# CW-LINK.net
KiCad netlist of a schematic drawn in EasyEDA Pro
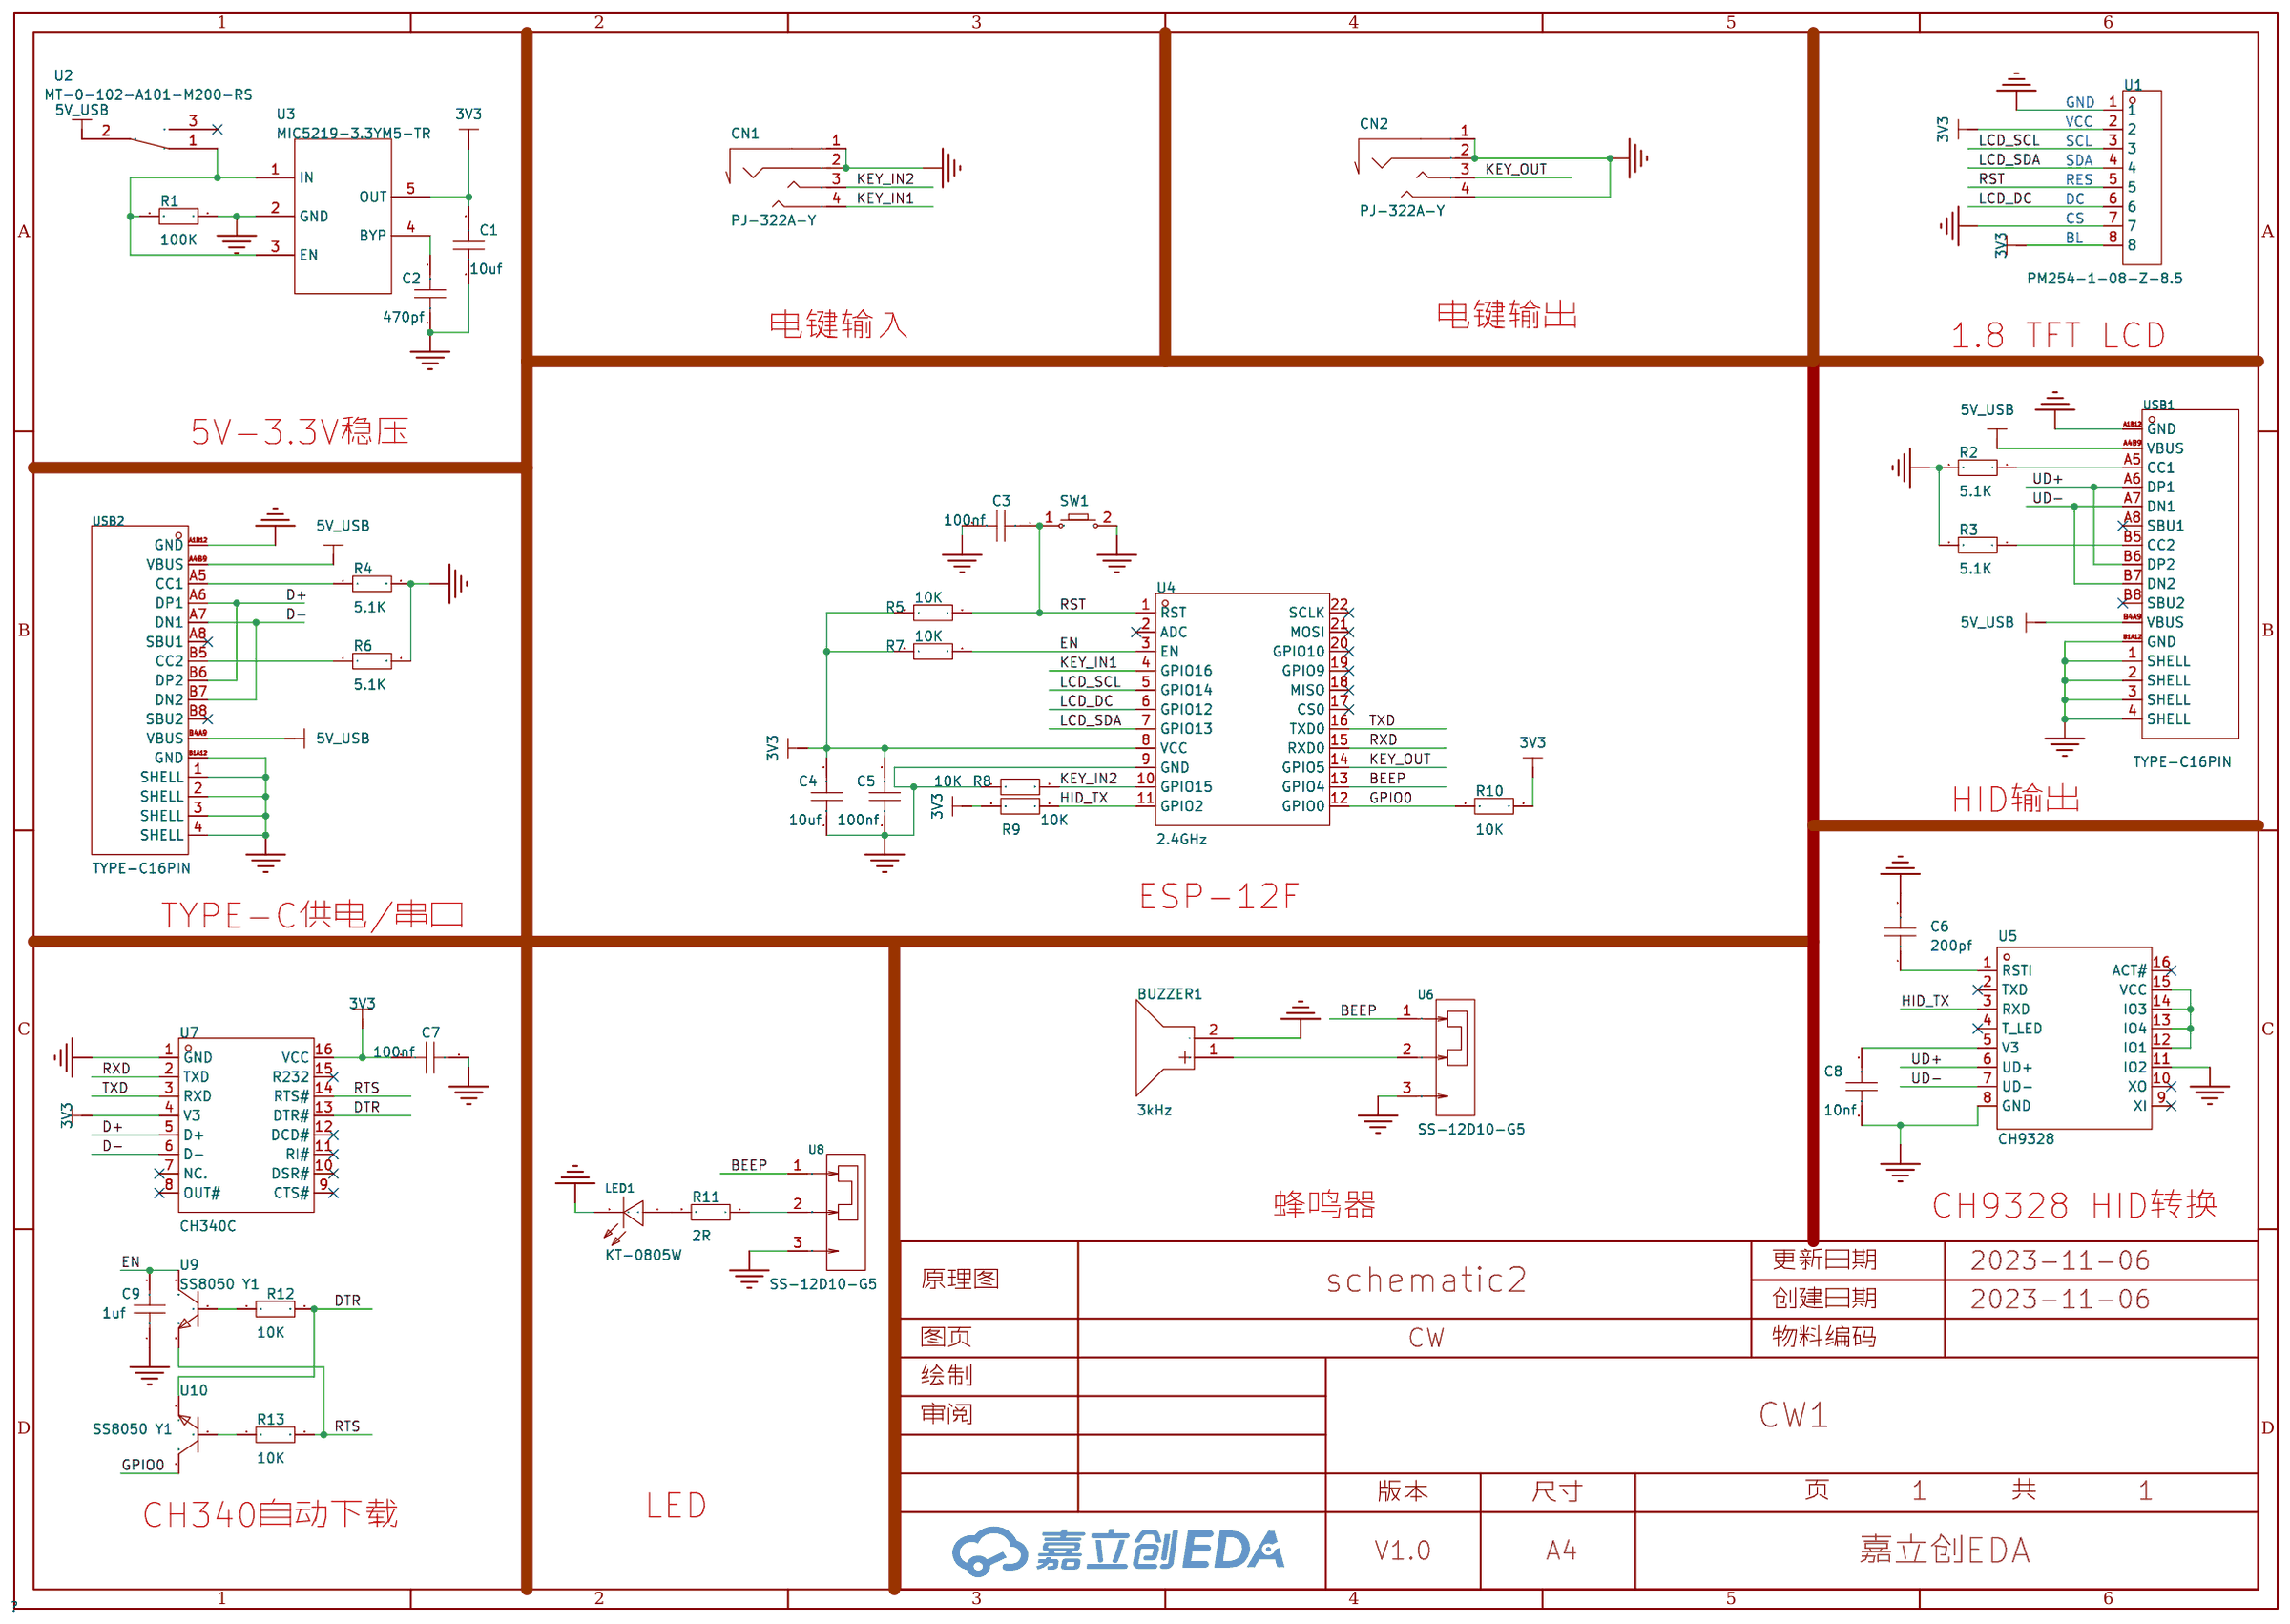
[diagram p0: schematic sheet]

(export (version "E")
  (design (tool "Eeschema 10.0.6"))
  (components
    (comp (ref "BUZZER1")
      (value "3kHz")
      (footprint "easyedapro:BUZ-TH_BD9.0-P5.00-D0.6-FD")
      (fields (field (name "Manufacturer Part") "HNB09A03") (field (name "Manufacturer") "华能"))
      (libsource (lib "easyedapro") (part "HNB09A03"))
    )
    (comp (ref "C1")
      (value "10uf")
      (footprint "easyedapro:C0603")
      (libsource (lib "easyedapro") (part "CapAcitance"))
    )
    (comp (ref "C2")
      (value "470pf")
      (footprint "easyedapro:C0603")
      (libsource (lib "easyedapro") (part "CapAcitance"))
    )
    (comp (ref "C3")
      (value "100nf")
      (footprint "easyedapro:C0603")
      (libsource (lib "easyedapro") (part "CapAcitance"))
    )
    (comp (ref "C4")
      (value "10uf")
      (footprint "easyedapro:C0603")
      (libsource (lib "easyedapro") (part "CapAcitance"))
    )
    (comp (ref "C5")
      (value "100nf")
      (footprint "easyedapro:C0603")
      (libsource (lib "easyedapro") (part "CapAcitance"))
    )
    (comp (ref "C6")
      (value "200pf")
      (footprint "easyedapro:C0603")
      (libsource (lib "easyedapro") (part "CapAcitance"))
    )
    (comp (ref "C7")
      (value "100nf")
      (footprint "easyedapro:C0603")
      (libsource (lib "easyedapro") (part "CapAcitance"))
    )
    (comp (ref "C8")
      (value "10nf")
      (footprint "easyedapro:C0603")
      (libsource (lib "easyedapro") (part "CapAcitance"))
    )
    (comp (ref "C9")
      (value "1uf")
      (footprint "easyedapro:C0603")
      (libsource (lib "easyedapro") (part "CapAcitance"))
    )
    (comp (ref "CN1")
      (value "PJ-322A-Y")
      (footprint "easyedapro:AUDIO-TH_PJ-322A-Y")
      (description "连接器类型:3.5mm耳机座;额定电流:500mA;额定电压:30V;工作温度范围:-20°C~+70°C;焊接温度(最大值):235°C;")
      (fields (field (name "Manufacturer") "XKB Connectivity(中国星坤)"))
      (libsource (lib "easyedapro") (part "PJ-322A-Y"))
    )
    (comp (ref "CN2")
      (value "PJ-322A-Y")
      (footprint "easyedapro:AUDIO-TH_PJ-322A-Y")
      (description "连接器类型:3.5mm耳机座;额定电流:500mA;额定电压:30V;工作温度范围:-20°C~+70°C;焊接温度(最大值):235°C;")
      (fields (field (name "Manufacturer") "XKB Connectivity(中国星坤)"))
      (libsource (lib "easyedapro") (part "PJ-322A-Y"))
    )
    (comp (ref "LED1")
      (value "KT-0805W")
      (footprint "easyedapro:LED0805-R-RD")
      (description "色温6000K左右")
      (fields (field (name "Manufacturer") "KENTO"))
      (libsource (lib "easyedapro") (part "whiteLEDSMD"))
    )
    (comp (ref "R1") (value "100K") (footprint "easyedapro:R0603") (libsource (lib "easyedapro") (part "电阻")))
    (comp (ref "R2") (value "5.1K") (footprint "easyedapro:R0603") (libsource (lib "easyedapro") (part "电阻")))
    (comp (ref "R3") (value "5.1K") (footprint "easyedapro:R0603") (libsource (lib "easyedapro") (part "电阻")))
    (comp (ref "R4") (value "5.1K") (footprint "easyedapro:R0603") (libsource (lib "easyedapro") (part "电阻")))
    (comp (ref "R5") (value "10K") (footprint "easyedapro:R0603") (libsource (lib "easyedapro") (part "电阻")))
    (comp (ref "R6") (value "5.1K") (footprint "easyedapro:R0603") (libsource (lib "easyedapro") (part "电阻")))
    (comp (ref "R7") (value "10K") (footprint "easyedapro:R0603") (libsource (lib "easyedapro") (part "电阻")))
    (comp (ref "R8") (value "10K") (footprint "easyedapro:R0603") (libsource (lib "easyedapro") (part "电阻")))
    (comp (ref "R9") (value "10K") (footprint "easyedapro:R0603") (libsource (lib "easyedapro") (part "电阻")))
    (comp (ref "R10") (value "10K") (footprint "easyedapro:R0603") (libsource (lib "easyedapro") (part "电阻")))
    (comp (ref "R11") (value "2R") (footprint "easyedapro:R0603") (libsource (lib "easyedapro") (part "电阻")))
    (comp (ref "R12") (value "10K") (footprint "easyedapro:R0603") (libsource (lib "easyedapro") (part "电阻")))
    (comp (ref "R13") (value "10K") (footprint "easyedapro:R0603") (libsource (lib "easyedapro") (part "电阻")))
    (comp (ref "SW1")
      (value "~")
      (footprint "easyedapro:Key_SMD_3x4x2")
      (libsource (lib "easyedapro") (part "轻触按键x2"))
    )
    (comp (ref "U1")
      (value "PM254-1-08-Z-8.5")
      (footprint "easyedapro:HDR-TH_8P-P2.54-V-F")
      (fields (field (name "Manufacturer") "HCTL(华灿天禄)"))
      (libsource (lib "easyedapro") (part "PM254-1-08-Z-8.5"))
    )
    (comp (ref "U2")
      (value "MT-0-102-A101-M200-RS")
      (footprint "easyedapro:SW-TH_MT-0-103-A101-M200-RS")
      (description "额定电流:5A;额定电压(AC):125V;电路结构:单刀双掷;机械寿命:-;安装方式:直插;")
      (fields (field (name "Manufacturer") "YUEN FUNG(源丰)"))
      (libsource (lib "easyedapro") (part "MT-0-102-A101-M200-RS+PJ"))
    )
    (comp (ref "U3")
      (value "MIC5219-3.3YM5-TR")
      (footprint "easyedapro:SOT-23-5_L3.0-W1.7-P0.95-LS2.8-TL")
      (description "输出类型:-;")
      (fields (field (name "Manufacturer") "MICROCHIP(美国微芯)"))
      (libsource (lib "easyedapro") (part "MIC5219-3.3YM5"))
    )
    (comp (ref "U4")
      (value "2.4GHz")
      (footprint "easyedapro:WIFIM-SMD_ESP-12F-ESP8266MOD")
      (description "频率:2.4GHz;发射功率:16dBm;核心处理器:ESP8266;天线形式:PCB 板载天线;接收灵敏度:-90dBm;")
      (fields
        (field (name "Manufacturer Part") "ESP-12F(ESP8266MOD)")
        (field (name "Manufacturer") "Ai-Thinker(安信可)")
      )
      (libsource (lib "easyedapro") (part "ESP-12F(ESP8266MOD)"))
    )
    (comp (ref "U5")
      (value "CH9328")
      (footprint "easyedapro:SOP-16_L10.0-W3.9-P1.27-LS6.0-BL")
      (description "应用功能:收发器;接口协议:USB 2.0;数据速率:12Mbps;")
      (fields (field (name "Manufacturer") "WCH(南京沁恒)"))
      (libsource (lib "easyedapro") (part "CH9328"))
    )
    (comp (ref "U6")
      (value "SS-12D10-G5")
      (footprint "easyedapro:SW-TH_SS-12D10-G050")
      (description "电路结构:单刀双掷;安装方式:直插;机械寿命:-;开关颜色:黑色;")
      (fields (field (name "Manufacturer") "DEALON(德艺隆)"))
      (libsource (lib "easyedapro") (part "SS-12D10-G5"))
    )
    (comp (ref "U7")
      (value "CH340C")
      (footprint "easyedapro:SOP-16_L10.0-W3.9-P1.27-LS6.0-BL")
      (description "应用功能:收发器;接口协议:USB 2.0;数据速率:2Mbps;")
      (fields (field (name "Manufacturer") "WCH(南京沁恒)"))
      (libsource (lib "easyedapro") (part "CH340C"))
    )
    (comp (ref "U8")
      (value "SS-12D10-G5")
      (footprint "easyedapro:SW-TH_SS-12D10-G050")
      (description "电路结构:单刀双掷;安装方式:直插;机械寿命:-;开关颜色:黑色;")
      (fields (field (name "Manufacturer") "DEALON(德艺隆)"))
      (libsource (lib "easyedapro") (part "SS-12D10-G5"))
    )
    (comp (ref "U9")
      (value "SS8050 Y1")
      (footprint "easyedapro:SOT-23-3_L2.9-W1.3-P1.90-LS2.4-BR")
      (description "晶体管类型:NPN;集射极击穿电压(Vceo):25V;集电极电流(Ic):1.5A;功率(Pd):300mW;直流电流增益(hFE@Ic,Vce):120@100mA,1V;")
      (fields (field (name "Manufacturer") "JUXING(钜兴)"))
      (libsource (lib "easyedapro") (part "SS8050 Y1"))
    )
    (comp (ref "U10")
      (value "SS8050 Y1")
      (footprint "easyedapro:SOT-23-3_L2.9-W1.3-P1.90-LS2.4-BR")
      (description "晶体管类型:NPN;集射极击穿电压(Vceo):25V;集电极电流(Ic):1.5A;功率(Pd):300mW;直流电流增益(hFE@Ic,Vce):120@100mA,1V;")
      (fields (field (name "Manufacturer") "JUXING(钜兴)"))
      (libsource (lib "easyedapro") (part "SS8050 Y1"))
    )
    (comp (ref "USB1")
      (value "TYPE-C16PIN")
      (footprint "easyedapro:USB-C-SMD_TYPE-C16PIN")
      (description "连接器类型:Type-C;标准:-;公母:母座;触点数量:16P;端口数量:1;安装方式:卧贴;额定电流 - 电源:3A;工作温度范围:-40°C~+85°C;")
      (fields (field (name "Manufacturer") "SHOU HAN(首韩)"))
      (libsource (lib "easyedapro") (part "TYPE-C16PIN"))
    )
    (comp (ref "USB2")
      (value "TYPE-C16PIN")
      (footprint "easyedapro:USB-C-SMD_TYPE-C16PIN")
      (description "连接器类型:Type-C;标准:-;公母:母座;触点数量:16P;端口数量:1;安装方式:卧贴;额定电流 - 电源:3A;工作温度范围:-40°C~+85°C;")
      (fields (field (name "Manufacturer") "SHOU HAN(首韩)"))
      (libsource (lib "easyedapro") (part "TYPE-C16PIN"))
    )
  )
  (nets
    (net (code "1") (name "/BEEP") (class "Default")
      (node (ref "U4") (pin "13") (pinfunction "GPIO4_13") (pintype "input"))
      (node (ref "U6") (pin "1") (pinfunction "1_1") (pintype "input"))
      (node (ref "U8") (pin "1") (pinfunction "1_1") (pintype "input"))
    )
    (net (code "2") (name "/D+") (class "Default")
      (node (ref "U7") (pin "5") (pinfunction "D+_5") (pintype "unspecified"))
      (node (ref "USB2") (pin "A6") (pinfunction "DP1_A6") (pintype "input"))
      (node (ref "USB2") (pin "B6") (pinfunction "DP2_B6") (pintype "input"))
    )
    (net (code "3") (name "/D-") (class "Default")
      (node (ref "U7") (pin "6") (pinfunction "D-_6") (pintype "unspecified"))
      (node (ref "USB2") (pin "A7") (pinfunction "DN1_A7") (pintype "input"))
      (node (ref "USB2") (pin "B7") (pinfunction "DN2_B7") (pintype "input"))
    )
    (net (code "4") (name "/DTR") (class "Default")
      (node (ref "R12") (pin "2") (pinfunction "2_2") (pintype "input"))
      (node (ref "U10") (pin "2") (pinfunction "E_2") (pintype "input"))
      (node (ref "U7") (pin "13") (pinfunction "DTR#_13") (pintype "unspecified"))
    )
    (net (code "5") (name "/EN") (class "Default")
      (node (ref "C9") (pin "2") (pinfunction "2_2") (pintype "input"))
      (node (ref "R7") (pin "2") (pinfunction "2_2") (pintype "input"))
      (node (ref "U4") (pin "3") (pinfunction "EN_3") (pintype "input"))
      (node (ref "U9") (pin "3") (pinfunction "C_3") (pintype "input"))
    )
    (net (code "6") (name "/GPIO0") (class "Default")
      (node (ref "R10") (pin "1") (pinfunction "1_1") (pintype "input"))
      (node (ref "U10") (pin "3") (pinfunction "C_3") (pintype "input"))
      (node (ref "U4") (pin "12") (pinfunction "GPIO0_12") (pintype "input"))
    )
    (net (code "7") (name "/HID_TX") (class "Default")
      (node (ref "R9") (pin "1") (pinfunction "1_1") (pintype "input"))
      (node (ref "U4") (pin "11") (pinfunction "GPIO2_11") (pintype "input"))
      (node (ref "U5") (pin "3") (pinfunction "RXD_3") (pintype "unspecified"))
    )
    (net (code "8") (name "/KEY_IN1") (class "Default")
      (node (ref "CN1") (pin "4") (pinfunction "4_4") (pintype "input"))
      (node (ref "U4") (pin "4") (pinfunction "GPIO16_4") (pintype "input"))
    )
    (net (code "9") (name "/KEY_IN2") (class "Default")
      (node (ref "CN1") (pin "3") (pinfunction "3_3") (pintype "input"))
      (node (ref "R8") (pin "2") (pinfunction "2_2") (pintype "input"))
      (node (ref "U4") (pin "10") (pinfunction "GPIO15_10") (pintype "input"))
    )
    (net (code "10") (name "/KEY_OUT") (class "Default")
      (node (ref "CN2") (pin "3") (pinfunction "3_3") (pintype "input"))
      (node (ref "U4") (pin "14") (pinfunction "GPIO5_14") (pintype "input"))
    )
    (net (code "11") (name "/LCD_DC") (class "Default")
      (node (ref "U1") (pin "6") (pinfunction "6_6") (pintype "unspecified"))
      (node (ref "U4") (pin "6") (pinfunction "GPIO12_6") (pintype "input"))
    )
    (net (code "12") (name "/LCD_SCL") (class "Default")
      (node (ref "U1") (pin "3") (pinfunction "3_3") (pintype "unspecified"))
      (node (ref "U4") (pin "5") (pinfunction "GPIO14_5") (pintype "input"))
    )
    (net (code "13") (name "/LCD_SDA") (class "Default")
      (node (ref "U1") (pin "4") (pinfunction "4_4") (pintype "unspecified"))
      (node (ref "U4") (pin "7") (pinfunction "GPIO13_7") (pintype "input"))
    )
    (net (code "14") (name "/RST") (class "Default")
      (node (ref "C3") (pin "1") (pinfunction "1_1") (pintype "input"))
      (node (ref "R5") (pin "2") (pinfunction "2_2") (pintype "input"))
      (node (ref "SW1") (pin "1") (pinfunction "1_1") (pintype "input"))
      (node (ref "U1") (pin "5") (pinfunction "5_5") (pintype "unspecified"))
      (node (ref "U4") (pin "1") (pinfunction "RST_1") (pintype "input"))
    )
    (net (code "15") (name "/RTS") (class "Default")
      (node (ref "R13") (pin "2") (pinfunction "2_2") (pintype "input"))
      (node (ref "U7") (pin "14") (pinfunction "RTS#_14") (pintype "unspecified"))
      (node (ref "U9") (pin "2") (pinfunction "E_2") (pintype "input"))
    )
    (net (code "16") (name "/RXD") (class "Default")
      (node (ref "U4") (pin "15") (pinfunction "RXD0_15") (pintype "input"))
      (node (ref "U7") (pin "2") (pinfunction "TXD_2") (pintype "unspecified"))
    )
    (net (code "17") (name "/TXD") (class "Default")
      (node (ref "U4") (pin "16") (pinfunction "TXD0_16") (pintype "input"))
      (node (ref "U7") (pin "3") (pinfunction "RXD_3") (pintype "unspecified"))
    )
    (net (code "18") (name "/UD+") (class "Default")
      (node (ref "U5") (pin "6") (pinfunction "UD+_6") (pintype "unspecified"))
      (node (ref "USB1") (pin "A6") (pinfunction "DP1_A6") (pintype "input"))
      (node (ref "USB1") (pin "B6") (pinfunction "DP2_B6") (pintype "input"))
    )
    (net (code "19") (name "/UD-") (class "Default")
      (node (ref "U5") (pin "7") (pinfunction "UD-_7") (pintype "unspecified"))
      (node (ref "USB1") (pin "A7") (pinfunction "DN1_A7") (pintype "input"))
      (node (ref "USB1") (pin "B7") (pinfunction "DN2_B7") (pintype "input"))
    )
    (net (code "20") (name "3V3") (class "Default")
      (node (ref "C1") (pin "2") (pinfunction "2_2") (pintype "input"))
      (node (ref "C4") (pin "2") (pinfunction "2_2") (pintype "input"))
      (node (ref "C5") (pin "2") (pinfunction "2_2") (pintype "input"))
      (node (ref "C7") (pin "1") (pinfunction "1_1") (pintype "input"))
      (node (ref "R10") (pin "2") (pinfunction "2_2") (pintype "input"))
      (node (ref "R5") (pin "1") (pinfunction "1_1") (pintype "input"))
      (node (ref "R7") (pin "1") (pinfunction "1_1") (pintype "input"))
      (node (ref "R9") (pin "2") (pinfunction "2_2") (pintype "input"))
      (node (ref "U1") (pin "2") (pinfunction "2_2") (pintype "unspecified"))
      (node (ref "U1") (pin "8") (pinfunction "8_8") (pintype "unspecified"))
      (node (ref "U3") (pin "5") (pinfunction "OUT_5") (pintype "input"))
      (node (ref "U4") (pin "8") (pinfunction "VCC_8") (pintype "input"))
      (node (ref "U7") (pin "16") (pinfunction "VCC_16") (pintype "unspecified"))
      (node (ref "U7") (pin "4") (pinfunction "V3_4") (pintype "unspecified"))
    )
    (net (code "21") (name "5V_USB") (class "Default")
      (node (ref "U2") (pin "2") (pinfunction "2_2") (pintype "unspecified"))
      (node (ref "USB1") (pin "A4B9") (pinfunction "VBUS_A4B9") (pintype "input"))
      (node (ref "USB1") (pin "B4A9") (pinfunction "VBUS_B4A9") (pintype "input"))
      (node (ref "USB2") (pin "A4B9") (pinfunction "VBUS_A4B9") (pintype "input"))
      (node (ref "USB2") (pin "B4A9") (pinfunction "VBUS_B4A9") (pintype "input"))
    )
    (net (code "22") (name "GND") (class "Default")
      (node (ref "BUZZER1") (pin "2") (pinfunction "-_2") (pintype "input"))
      (node (ref "C1") (pin "1") (pinfunction "1_1") (pintype "input"))
      (node (ref "C2") (pin "1") (pinfunction "1_1") (pintype "input"))
      (node (ref "C3") (pin "2") (pinfunction "2_2") (pintype "input"))
      (node (ref "C4") (pin "1") (pinfunction "1_1") (pintype "input"))
      (node (ref "C5") (pin "1") (pinfunction "1_1") (pintype "input"))
      (node (ref "C6") (pin "2") (pinfunction "2_2") (pintype "input"))
      (node (ref "C7") (pin "2") (pinfunction "2_2") (pintype "input"))
      (node (ref "C8") (pin "1") (pinfunction "1_1") (pintype "input"))
      (node (ref "C9") (pin "1") (pinfunction "1_1") (pintype "input"))
      (node (ref "CN1") (pin "1") (pinfunction "1_1") (pintype "input"))
      (node (ref "CN1") (pin "2") (pinfunction "2_2") (pintype "input"))
      (node (ref "CN2") (pin "1") (pinfunction "1_1") (pintype "input"))
      (node (ref "CN2") (pin "2") (pinfunction "2_2") (pintype "input"))
      (node (ref "CN2") (pin "4") (pinfunction "4_4") (pintype "input"))
      (node (ref "LED1") (pin "2") (pinfunction "K_2") (pintype "input"))
      (node (ref "R1") (pin "1") (pinfunction "1_1") (pintype "input"))
      (node (ref "R2") (pin "2") (pinfunction "2_2") (pintype "input"))
      (node (ref "R3") (pin "2") (pinfunction "2_2") (pintype "input"))
      (node (ref "R4") (pin "2") (pinfunction "2_2") (pintype "input"))
      (node (ref "R6") (pin "2") (pinfunction "2_2") (pintype "input"))
      (node (ref "R8") (pin "1") (pinfunction "1_1") (pintype "input"))
      (node (ref "SW1") (pin "2") (pinfunction "2_2") (pintype "input"))
      (node (ref "U1") (pin "1") (pinfunction "1_1") (pintype "unspecified"))
      (node (ref "U1") (pin "7") (pinfunction "7_7") (pintype "unspecified"))
      (node (ref "U3") (pin "2") (pinfunction "GND_2") (pintype "input"))
      (node (ref "U4") (pin "9") (pinfunction "GND_9") (pintype "input"))
      (node (ref "U5") (pin "11") (pinfunction "IO2_11") (pintype "unspecified"))
      (node (ref "U5") (pin "8") (pinfunction "GND_8") (pintype "unspecified"))
      (node (ref "U6") (pin "3") (pinfunction "3_3") (pintype "input"))
      (node (ref "U7") (pin "1") (pinfunction "GND_1") (pintype "unspecified"))
      (node (ref "U8") (pin "3") (pinfunction "3_3") (pintype "input"))
      (node (ref "USB1") (pin "1") (pinfunction "SHELL_1") (pintype "input"))
      (node (ref "USB1") (pin "2") (pinfunction "SHELL_2") (pintype "input"))
      (node (ref "USB1") (pin "3") (pinfunction "SHELL_3") (pintype "input"))
      (node (ref "USB1") (pin "4") (pinfunction "SHELL_4") (pintype "input"))
      (node (ref "USB1") (pin "A1B12") (pinfunction "GND_A1B12") (pintype "input"))
      (node (ref "USB1") (pin "B1A12") (pinfunction "GND_B1A12") (pintype "input"))
      (node (ref "USB2") (pin "1") (pinfunction "SHELL_1") (pintype "input"))
      (node (ref "USB2") (pin "2") (pinfunction "SHELL_2") (pintype "input"))
      (node (ref "USB2") (pin "3") (pinfunction "SHELL_3") (pintype "input"))
      (node (ref "USB2") (pin "4") (pinfunction "SHELL_4") (pintype "input"))
      (node (ref "USB2") (pin "A1B12") (pinfunction "GND_A1B12") (pintype "input"))
      (node (ref "USB2") (pin "B1A12") (pinfunction "GND_B1A12") (pintype "input"))
    )
    (net (code "23") (name "Net-(BUZZER1-+)") (class "Default")
      (node (ref "BUZZER1") (pin "1") (pinfunction "+_1") (pintype "input"))
      (node (ref "U6") (pin "2") (pinfunction "2_2") (pintype "input"))
    )
    (net (code "24") (name "Net-(LED1-A)") (class "Default")
      (node (ref "LED1") (pin "1") (pinfunction "A_1") (pintype "input"))
      (node (ref "R11") (pin "2") (pinfunction "2_2") (pintype "input"))
    )
    (net (code "25") (name "Net-(R11-Pad1)") (class "Default")
      (node (ref "R11") (pin "1") (pinfunction "1_1") (pintype "input"))
      (node (ref "U8") (pin "2") (pinfunction "2_2") (pintype "input"))
    )
    (net (code "26") (name "Net-(U3-BYP)") (class "Default")
      (node (ref "C2") (pin "2") (pinfunction "2_2") (pintype "input"))
      (node (ref "U3") (pin "4") (pinfunction "BYP_4") (pintype "input"))
    )
    (net (code "27") (name "Net-(U3-EN)") (class "Default")
      (node (ref "R1") (pin "2") (pinfunction "2_2") (pintype "input"))
      (node (ref "U2") (pin "1") (pinfunction "1_1") (pintype "unspecified"))
      (node (ref "U3") (pin "1") (pinfunction "IN_1") (pintype "input"))
      (node (ref "U3") (pin "3") (pinfunction "EN_3") (pintype "input"))
    )
    (net (code "28") (name "Net-(U5-IO1)") (class "Default")
      (node (ref "U5") (pin "12") (pinfunction "IO1_12") (pintype "unspecified"))
      (node (ref "U5") (pin "13") (pinfunction "IO4_13") (pintype "unspecified"))
      (node (ref "U5") (pin "14") (pinfunction "IO3_14") (pintype "unspecified"))
      (node (ref "U5") (pin "15") (pinfunction "VCC_15") (pintype "unspecified"))
    )
    (net (code "29") (name "Net-(U5-RSTI)") (class "Default")
      (node (ref "C6") (pin "1") (pinfunction "1_1") (pintype "input"))
      (node (ref "U5") (pin "1") (pinfunction "RSTI_1") (pintype "unspecified"))
    )
    (net (code "30") (name "Net-(U5-V3)") (class "Default")
      (node (ref "C8") (pin "2") (pinfunction "2_2") (pintype "input"))
      (node (ref "U5") (pin "5") (pinfunction "V3_5") (pintype "unspecified"))
    )
    (net (code "31") (name "Net-(U9-B)") (class "Default")
      (node (ref "R12") (pin "1") (pinfunction "1_1") (pintype "input"))
      (node (ref "U9") (pin "1") (pinfunction "B_1") (pintype "input"))
    )
    (net (code "32") (name "Net-(U10-B)") (class "Default")
      (node (ref "R13") (pin "1") (pinfunction "1_1") (pintype "input"))
      (node (ref "U10") (pin "1") (pinfunction "B_1") (pintype "input"))
    )
    (net (code "33") (name "Net-(USB1-CC1)") (class "Default")
      (node (ref "R2") (pin "1") (pinfunction "1_1") (pintype "input"))
      (node (ref "USB1") (pin "A5") (pinfunction "CC1_A5") (pintype "input"))
    )
    (net (code "34") (name "Net-(USB1-CC2)") (class "Default")
      (node (ref "R3") (pin "1") (pinfunction "1_1") (pintype "input"))
      (node (ref "USB1") (pin "B5") (pinfunction "CC2_B5") (pintype "input"))
    )
    (net (code "35") (name "Net-(USB2-CC1)") (class "Default")
      (node (ref "R4") (pin "1") (pinfunction "1_1") (pintype "input"))
      (node (ref "USB2") (pin "A5") (pinfunction "CC1_A5") (pintype "input"))
    )
    (net (code "36") (name "Net-(USB2-CC2)") (class "Default")
      (node (ref "R6") (pin "1") (pinfunction "1_1") (pintype "input"))
      (node (ref "USB2") (pin "B5") (pinfunction "CC2_B5") (pintype "input"))
    )
    (net (code "37") (name "unconnected-(U2-Pad3)") (class "Default")
      (node (ref "U2") (pin "3") (pinfunction "3_3") (pintype "unspecified+no_connect"))
    )
    (net (code "38") (name "unconnected-(U4-ADC-Pad2)") (class "Default")
      (node (ref "U4") (pin "2") (pinfunction "ADC_2") (pintype "input+no_connect"))
    )
    (net (code "39") (name "unconnected-(U4-CS0-Pad17)") (class "Default")
      (node (ref "U4") (pin "17") (pinfunction "CS0_17") (pintype "input+no_connect"))
    )
    (net (code "40") (name "unconnected-(U4-GPIO9-Pad19)") (class "Default")
      (node (ref "U4") (pin "19") (pinfunction "GPIO9_19") (pintype "input+no_connect"))
    )
    (net (code "41") (name "unconnected-(U4-GPIO10-Pad20)") (class "Default")
      (node (ref "U4") (pin "20") (pinfunction "GPIO10_20") (pintype "input+no_connect"))
    )
    (net (code "42") (name "unconnected-(U4-MISO-Pad18)") (class "Default")
      (node (ref "U4") (pin "18") (pinfunction "MISO_18") (pintype "input+no_connect"))
    )
    (net (code "43") (name "unconnected-(U4-MOSI-Pad21)") (class "Default")
      (node (ref "U4") (pin "21") (pinfunction "MOSI_21") (pintype "input+no_connect"))
    )
    (net (code "44") (name "unconnected-(U4-SCLK-Pad22)") (class "Default")
      (node (ref "U4") (pin "22") (pinfunction "SCLK_22") (pintype "input+no_connect"))
    )
    (net (code "45") (name "unconnected-(U5-ACT#-Pad16)") (class "Default")
      (node (ref "U5") (pin "16") (pinfunction "ACT#_16") (pintype "unspecified+no_connect"))
    )
    (net (code "46") (name "unconnected-(U5-TXD-Pad2)") (class "Default")
      (node (ref "U5") (pin "2") (pinfunction "TXD_2") (pintype "unspecified+no_connect"))
    )
    (net (code "47") (name "unconnected-(U5-T_LED-Pad4)") (class "Default")
      (node (ref "U5") (pin "4") (pinfunction "T_LED_4") (pintype "unspecified+no_connect"))
    )
    (net (code "48") (name "unconnected-(U5-XI-Pad9)") (class "Default")
      (node (ref "U5") (pin "9") (pinfunction "XI_9") (pintype "unspecified+no_connect"))
    )
    (net (code "49") (name "unconnected-(U5-XO-Pad10)") (class "Default")
      (node (ref "U5") (pin "10") (pinfunction "XO_10") (pintype "unspecified+no_connect"))
    )
    (net (code "50") (name "unconnected-(U7-CTS#-Pad9)") (class "Default")
      (node (ref "U7") (pin "9") (pinfunction "CTS#_9") (pintype "unspecified+no_connect"))
    )
    (net (code "51") (name "unconnected-(U7-DCD#-Pad12)") (class "Default")
      (node (ref "U7") (pin "12") (pinfunction "DCD#_12") (pintype "unspecified+no_connect"))
    )
    (net (code "52") (name "unconnected-(U7-DSR#-Pad10)") (class "Default")
      (node (ref "U7") (pin "10") (pinfunction "DSR#_10") (pintype "unspecified+no_connect"))
    )
    (net (code "53") (name "unconnected-(U7-NC.-Pad7)") (class "Default")
      (node (ref "U7") (pin "7") (pinfunction "NC._7") (pintype "unspecified+no_connect"))
    )
    (net (code "54") (name "unconnected-(U7-OUT#-Pad8)") (class "Default")
      (node (ref "U7") (pin "8") (pinfunction "OUT#_8") (pintype "unspecified+no_connect"))
    )
    (net (code "55") (name "unconnected-(U7-R232-Pad15)") (class "Default")
      (node (ref "U7") (pin "15") (pinfunction "R232_15") (pintype "unspecified+no_connect"))
    )
    (net (code "56") (name "unconnected-(U7-RI#-Pad11)") (class "Default")
      (node (ref "U7") (pin "11") (pinfunction "RI#_11") (pintype "unspecified+no_connect"))
    )
    (net (code "57") (name "unconnected-(USB1-SBU1-PadA8)") (class "Default")
      (node (ref "USB1") (pin "A8") (pinfunction "SBU1_A8") (pintype "input+no_connect"))
    )
    (net (code "58") (name "unconnected-(USB1-SBU2-PadB8)") (class "Default")
      (node (ref "USB1") (pin "B8") (pinfunction "SBU2_B8") (pintype "input+no_connect"))
    )
    (net (code "59") (name "unconnected-(USB2-SBU1-PadA8)") (class "Default")
      (node (ref "USB2") (pin "A8") (pinfunction "SBU1_A8") (pintype "input+no_connect"))
    )
    (net (code "60") (name "unconnected-(USB2-SBU2-PadB8)") (class "Default")
      (node (ref "USB2") (pin "B8") (pinfunction "SBU2_B8") (pintype "input+no_connect"))
    )
  )
)
